# rca-board.net
KiCad netlist of a schematic drawn in EAGLE
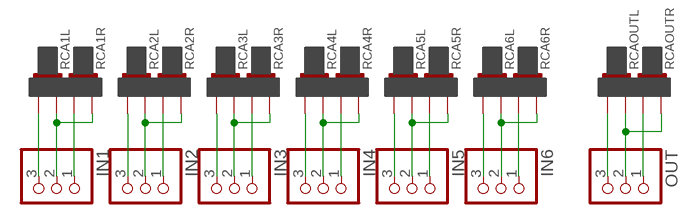
[diagram p0: schematic, sheet 1]

(export (version "E")
  (design (tool "Eeschema 10.0.6"))
  (components
    (comp (ref "IN1")
      (value "PINHD-1X3")
      (footprint "eagle-import:1X03")
      (libsource (lib "eagle-import") (part "PINHD-1X3"))
    )
    (comp (ref "IN2")
      (value "PINHD-1X3")
      (footprint "eagle-import:1X03")
      (libsource (lib "eagle-import") (part "PINHD-1X3"))
    )
    (comp (ref "IN3")
      (value "PINHD-1X3")
      (footprint "eagle-import:1X03")
      (libsource (lib "eagle-import") (part "PINHD-1X3"))
    )
    (comp (ref "IN4")
      (value "PINHD-1X3")
      (footprint "eagle-import:1X03")
      (libsource (lib "eagle-import") (part "PINHD-1X3"))
    )
    (comp (ref "IN5")
      (value "PINHD-1X3")
      (footprint "eagle-import:1X03")
      (libsource (lib "eagle-import") (part "PINHD-1X3"))
    )
    (comp (ref "IN6")
      (value "PINHD-1X3")
      (footprint "eagle-import:1X03")
      (libsource (lib "eagle-import") (part "PINHD-1X3"))
    )
    (comp (ref "OUT")
      (value "PINHD-1X3")
      (footprint "eagle-import:1X03")
      (libsource (lib "eagle-import") (part "PINHD-1X3"))
    )
    (comp (ref "RCA1L")
      (value "CMC_RCA816")
      (footprint "eagle-import:CMC_RCA_816")
      (libsource (lib "eagle-import") (part "CMC_RCA816"))
    )
    (comp (ref "RCA1R")
      (value "CMC_RCA816")
      (footprint "eagle-import:CMC_RCA_816")
      (libsource (lib "eagle-import") (part "CMC_RCA816"))
    )
    (comp (ref "RCA2L")
      (value "CMC_RCA816")
      (footprint "eagle-import:CMC_RCA_816")
      (libsource (lib "eagle-import") (part "CMC_RCA816"))
    )
    (comp (ref "RCA2R")
      (value "CMC_RCA816")
      (footprint "eagle-import:CMC_RCA_816")
      (libsource (lib "eagle-import") (part "CMC_RCA816"))
    )
    (comp (ref "RCA3L")
      (value "CMC_RCA816")
      (footprint "eagle-import:CMC_RCA_816")
      (libsource (lib "eagle-import") (part "CMC_RCA816"))
    )
    (comp (ref "RCA3R")
      (value "CMC_RCA816")
      (footprint "eagle-import:CMC_RCA_816")
      (libsource (lib "eagle-import") (part "CMC_RCA816"))
    )
    (comp (ref "RCA4L")
      (value "CMC_RCA816")
      (footprint "eagle-import:CMC_RCA_816")
      (libsource (lib "eagle-import") (part "CMC_RCA816"))
    )
    (comp (ref "RCA4R")
      (value "CMC_RCA816")
      (footprint "eagle-import:CMC_RCA_816")
      (libsource (lib "eagle-import") (part "CMC_RCA816"))
    )
    (comp (ref "RCA5L")
      (value "CMC_RCA816")
      (footprint "eagle-import:CMC_RCA_816")
      (libsource (lib "eagle-import") (part "CMC_RCA816"))
    )
    (comp (ref "RCA5R")
      (value "CMC_RCA816")
      (footprint "eagle-import:CMC_RCA_816")
      (libsource (lib "eagle-import") (part "CMC_RCA816"))
    )
    (comp (ref "RCA6L")
      (value "CMC_RCA816")
      (footprint "eagle-import:CMC_RCA_816")
      (libsource (lib "eagle-import") (part "CMC_RCA816"))
    )
    (comp (ref "RCA6R")
      (value "CMC_RCA816")
      (footprint "eagle-import:CMC_RCA_816")
      (libsource (lib "eagle-import") (part "CMC_RCA816"))
    )
    (comp (ref "RCAOUTL")
      (value "CMC_RCA816")
      (footprint "eagle-import:CMC_RCA_816")
      (libsource (lib "eagle-import") (part "CMC_RCA816"))
    )
    (comp (ref "RCAOUTR")
      (value "CMC_RCA816")
      (footprint "eagle-import:CMC_RCA_816")
      (libsource (lib "eagle-import") (part "CMC_RCA816"))
    )
  )
  (nets
    (net (code "1") (name "Net-(IN1-Pad1)") (class "Default")
      (node (ref "IN1") (pin "1") (pinfunction "1_1") (pintype "passive"))
      (node (ref "RCA1R") (pin "SIGNAL") (pinfunction "SIGNAL_SIGNAL") (pintype "bidirectional"))
    )
    (net (code "2") (name "Net-(IN1-Pad2)") (class "Default")
      (node (ref "IN1") (pin "2") (pinfunction "2_2") (pintype "passive"))
      (node (ref "RCA1L") (pin "GND") (pinfunction "GND_GND") (pintype "bidirectional"))
      (node (ref "RCA1R") (pin "GND") (pinfunction "GND_GND") (pintype "bidirectional"))
    )
    (net (code "3") (name "Net-(IN1-Pad3)") (class "Default")
      (node (ref "IN1") (pin "3") (pinfunction "3_3") (pintype "passive"))
      (node (ref "RCA1L") (pin "SIGNAL") (pinfunction "SIGNAL_SIGNAL") (pintype "bidirectional"))
    )
    (net (code "4") (name "Net-(IN2-Pad1)") (class "Default")
      (node (ref "IN2") (pin "1") (pinfunction "1_1") (pintype "passive"))
      (node (ref "RCA2R") (pin "SIGNAL") (pinfunction "SIGNAL_SIGNAL") (pintype "bidirectional"))
    )
    (net (code "5") (name "Net-(IN2-Pad2)") (class "Default")
      (node (ref "IN2") (pin "2") (pinfunction "2_2") (pintype "passive"))
      (node (ref "RCA2L") (pin "GND") (pinfunction "GND_GND") (pintype "bidirectional"))
      (node (ref "RCA2R") (pin "GND") (pinfunction "GND_GND") (pintype "bidirectional"))
    )
    (net (code "6") (name "Net-(IN2-Pad3)") (class "Default")
      (node (ref "IN2") (pin "3") (pinfunction "3_3") (pintype "passive"))
      (node (ref "RCA2L") (pin "SIGNAL") (pinfunction "SIGNAL_SIGNAL") (pintype "bidirectional"))
    )
    (net (code "7") (name "Net-(IN3-Pad1)") (class "Default")
      (node (ref "IN3") (pin "1") (pinfunction "1_1") (pintype "passive"))
      (node (ref "RCA3R") (pin "SIGNAL") (pinfunction "SIGNAL_SIGNAL") (pintype "bidirectional"))
    )
    (net (code "8") (name "Net-(IN3-Pad2)") (class "Default")
      (node (ref "IN3") (pin "2") (pinfunction "2_2") (pintype "passive"))
      (node (ref "RCA3L") (pin "GND") (pinfunction "GND_GND") (pintype "bidirectional"))
      (node (ref "RCA3R") (pin "GND") (pinfunction "GND_GND") (pintype "bidirectional"))
    )
    (net (code "9") (name "Net-(IN3-Pad3)") (class "Default")
      (node (ref "IN3") (pin "3") (pinfunction "3_3") (pintype "passive"))
      (node (ref "RCA3L") (pin "SIGNAL") (pinfunction "SIGNAL_SIGNAL") (pintype "bidirectional"))
    )
    (net (code "10") (name "Net-(IN4-Pad1)") (class "Default")
      (node (ref "IN4") (pin "1") (pinfunction "1_1") (pintype "passive"))
      (node (ref "RCA4R") (pin "SIGNAL") (pinfunction "SIGNAL_SIGNAL") (pintype "bidirectional"))
    )
    (net (code "11") (name "Net-(IN4-Pad2)") (class "Default")
      (node (ref "IN4") (pin "2") (pinfunction "2_2") (pintype "passive"))
      (node (ref "RCA4L") (pin "GND") (pinfunction "GND_GND") (pintype "bidirectional"))
      (node (ref "RCA4R") (pin "GND") (pinfunction "GND_GND") (pintype "bidirectional"))
    )
    (net (code "12") (name "Net-(IN4-Pad3)") (class "Default")
      (node (ref "IN4") (pin "3") (pinfunction "3_3") (pintype "passive"))
      (node (ref "RCA4L") (pin "SIGNAL") (pinfunction "SIGNAL_SIGNAL") (pintype "bidirectional"))
    )
    (net (code "13") (name "Net-(IN5-Pad1)") (class "Default")
      (node (ref "IN5") (pin "1") (pinfunction "1_1") (pintype "passive"))
      (node (ref "RCA5R") (pin "SIGNAL") (pinfunction "SIGNAL_SIGNAL") (pintype "bidirectional"))
    )
    (net (code "14") (name "Net-(IN5-Pad2)") (class "Default")
      (node (ref "IN5") (pin "2") (pinfunction "2_2") (pintype "passive"))
      (node (ref "RCA5L") (pin "GND") (pinfunction "GND_GND") (pintype "bidirectional"))
      (node (ref "RCA5R") (pin "GND") (pinfunction "GND_GND") (pintype "bidirectional"))
    )
    (net (code "15") (name "Net-(IN5-Pad3)") (class "Default")
      (node (ref "IN5") (pin "3") (pinfunction "3_3") (pintype "passive"))
      (node (ref "RCA5L") (pin "SIGNAL") (pinfunction "SIGNAL_SIGNAL") (pintype "bidirectional"))
    )
    (net (code "16") (name "Net-(IN6-Pad1)") (class "Default")
      (node (ref "IN6") (pin "1") (pinfunction "1_1") (pintype "passive"))
      (node (ref "RCA6R") (pin "SIGNAL") (pinfunction "SIGNAL_SIGNAL") (pintype "bidirectional"))
    )
    (net (code "17") (name "Net-(IN6-Pad2)") (class "Default")
      (node (ref "IN6") (pin "2") (pinfunction "2_2") (pintype "passive"))
      (node (ref "RCA6L") (pin "GND") (pinfunction "GND_GND") (pintype "bidirectional"))
      (node (ref "RCA6R") (pin "GND") (pinfunction "GND_GND") (pintype "bidirectional"))
    )
    (net (code "18") (name "Net-(IN6-Pad3)") (class "Default")
      (node (ref "IN6") (pin "3") (pinfunction "3_3") (pintype "passive"))
      (node (ref "RCA6L") (pin "SIGNAL") (pinfunction "SIGNAL_SIGNAL") (pintype "bidirectional"))
    )
    (net (code "19") (name "Net-(OUT-Pad1)") (class "Default")
      (node (ref "OUT") (pin "1") (pinfunction "1_1") (pintype "passive"))
      (node (ref "RCAOUTR") (pin "SIGNAL") (pinfunction "SIGNAL_SIGNAL") (pintype "bidirectional"))
    )
    (net (code "20") (name "Net-(OUT-Pad2)") (class "Default")
      (node (ref "OUT") (pin "2") (pinfunction "2_2") (pintype "passive"))
      (node (ref "RCAOUTL") (pin "GND") (pinfunction "GND_GND") (pintype "bidirectional"))
      (node (ref "RCAOUTR") (pin "GND") (pinfunction "GND_GND") (pintype "bidirectional"))
    )
    (net (code "21") (name "Net-(OUT-Pad3)") (class "Default")
      (node (ref "OUT") (pin "3") (pinfunction "3_3") (pintype "passive"))
      (node (ref "RCAOUTL") (pin "SIGNAL") (pinfunction "SIGNAL_SIGNAL") (pintype "bidirectional"))
    )
  )
)
